# wifi_led.net
KiCad netlist of a schematic drawn in EAGLE
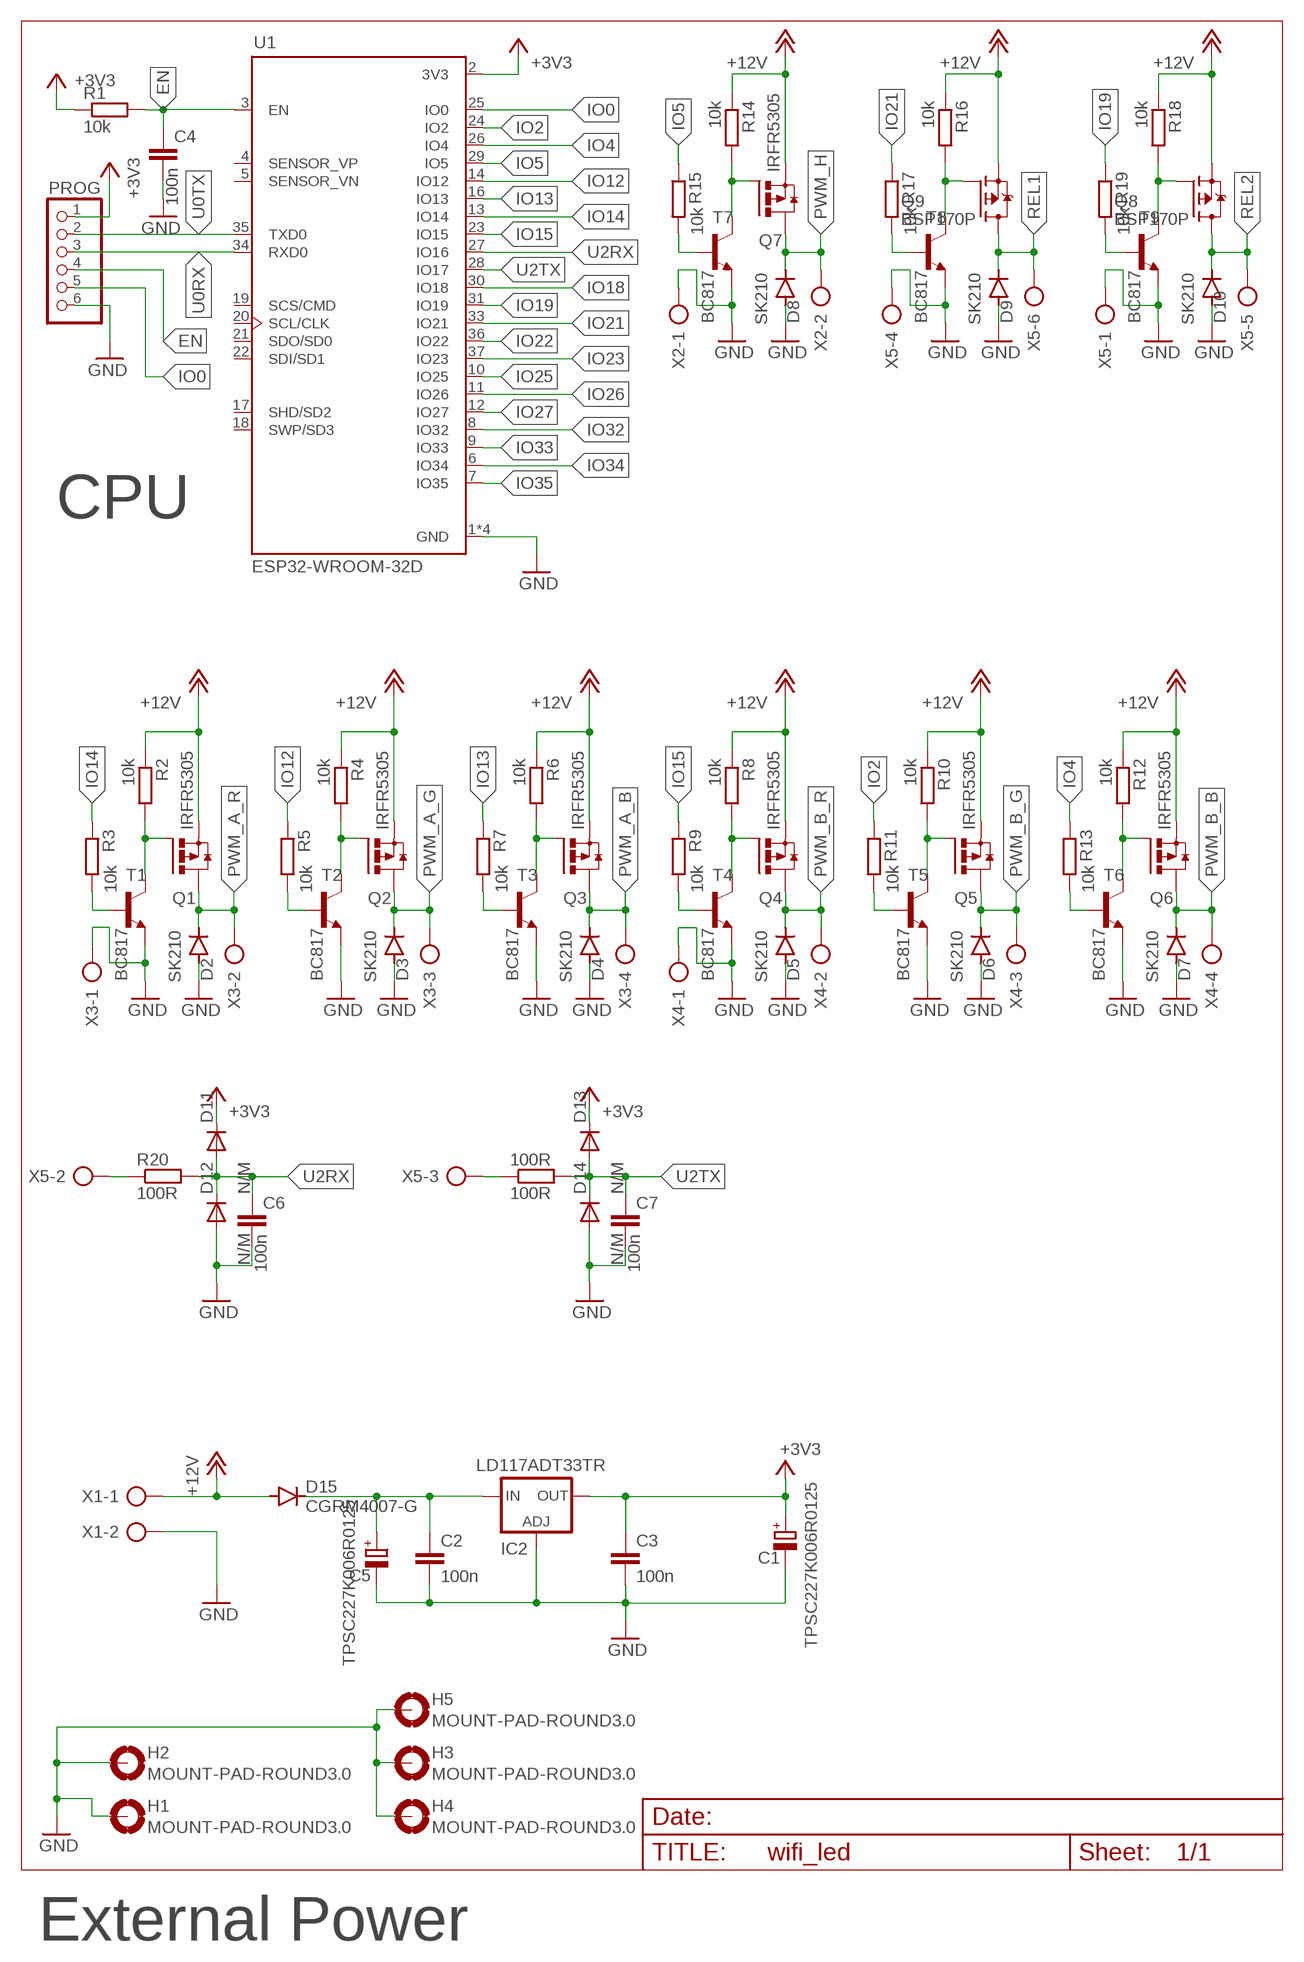
[diagram p0: schematic, sheet 1]

(export (version "E")
  (design (tool "Eeschema 10.0.6"))
  (components
    (comp (ref "100R")
      (value "100R")
      (footprint "eagle-import:R0603")
      (libsource (lib "eagle-import") (part "rcl_334_R-EU_R0603"))
    )
    (comp (ref "C1")
      (value "TPSC227K006R0125")
      (footprint "eagle-import:CT6032")
      (libsource (lib "eagle-import") (part "CPOL-EUCT6032"))
    )
    (comp (ref "C2")
      (value "100n")
      (footprint "eagle-import:C0603")
      (libsource (lib "eagle-import") (part "C-EUC0603"))
    )
    (comp (ref "C3")
      (value "100n")
      (footprint "eagle-import:C0603")
      (libsource (lib "eagle-import") (part "C-EUC0603"))
    )
    (comp (ref "C4")
      (value "100n")
      (footprint "eagle-import:C0603")
      (libsource (lib "eagle-import") (part "C-EUC0603"))
    )
    (comp (ref "C5")
      (value "TPSC227K006R0125")
      (footprint "eagle-import:CT6032")
      (libsource (lib "eagle-import") (part "CPOL-EUCT6032"))
    )
    (comp (ref "C6")
      (value "100n")
      (footprint "eagle-import:C0603")
      (libsource (lib "eagle-import") (part "C-EUC0603"))
    )
    (comp (ref "C7")
      (value "100n")
      (footprint "eagle-import:C0603")
      (libsource (lib "eagle-import") (part "C-EUC0603"))
    )
    (comp (ref "D2")
      (value "SK210")
      (footprint "eagle-import:SMB")
      (libsource (lib "eagle-import") (part "diode_210_DIODE-SMB"))
    )
    (comp (ref "D3")
      (value "SK210")
      (footprint "eagle-import:SMB")
      (libsource (lib "eagle-import") (part "diode_210_DIODE-SMB"))
    )
    (comp (ref "D4")
      (value "SK210")
      (footprint "eagle-import:SMB")
      (libsource (lib "eagle-import") (part "diode_210_DIODE-SMB"))
    )
    (comp (ref "D5")
      (value "SK210")
      (footprint "eagle-import:SMB")
      (libsource (lib "eagle-import") (part "diode_210_DIODE-SMB"))
    )
    (comp (ref "D6")
      (value "SK210")
      (footprint "eagle-import:SMB")
      (libsource (lib "eagle-import") (part "diode_210_DIODE-SMB"))
    )
    (comp (ref "D7")
      (value "SK210")
      (footprint "eagle-import:SMB")
      (libsource (lib "eagle-import") (part "diode_210_DIODE-SMB"))
    )
    (comp (ref "D8")
      (value "SK210")
      (footprint "eagle-import:SMB")
      (libsource (lib "eagle-import") (part "diode_210_DIODE-SMB"))
    )
    (comp (ref "D9")
      (value "SK210")
      (footprint "eagle-import:SMB")
      (libsource (lib "eagle-import") (part "diode_210_DIODE-SMB"))
    )
    (comp (ref "D10")
      (value "SK210")
      (footprint "eagle-import:SMB")
      (libsource (lib "eagle-import") (part "diode_210_DIODE-SMB"))
    )
    (comp (ref "D11")
      (value "N/M")
      (footprint "eagle-import:0603")
      (libsource (lib "eagle-import") (part "DIODE-SMD0603"))
    )
    (comp (ref "D12")
      (value "N/M")
      (footprint "eagle-import:0603")
      (libsource (lib "eagle-import") (part "DIODE-SMD0603"))
    )
    (comp (ref "D13")
      (value "N/M")
      (footprint "eagle-import:0603")
      (libsource (lib "eagle-import") (part "DIODE-SMD0603"))
    )
    (comp (ref "D14")
      (value "N/M")
      (footprint "eagle-import:0603")
      (libsource (lib "eagle-import") (part "DIODE-SMD0603"))
    )
    (comp (ref "D15")
      (value "CGRM4007-G")
      (footprint "eagle-import:SOD-123_MINI-SMA")
      (libsource (lib "eagle-import") (part "CGRM400-G7"))
    )
    (comp (ref "H1")
      (value "MOUNT-PAD-ROUND3.0")
      (footprint "eagle-import:3,0-PAD")
      (libsource (lib "eagle-import") (part "MOUNT-PAD-ROUND3.0"))
    )
    (comp (ref "H2")
      (value "MOUNT-PAD-ROUND3.0")
      (footprint "eagle-import:3,0-PAD")
      (libsource (lib "eagle-import") (part "MOUNT-PAD-ROUND3.0"))
    )
    (comp (ref "H3")
      (value "MOUNT-PAD-ROUND3.0")
      (footprint "eagle-import:3,0-PAD")
      (libsource (lib "eagle-import") (part "MOUNT-PAD-ROUND3.0"))
    )
    (comp (ref "H4")
      (value "MOUNT-PAD-ROUND3.0")
      (footprint "eagle-import:3,0-PAD")
      (libsource (lib "eagle-import") (part "MOUNT-PAD-ROUND3.0"))
    )
    (comp (ref "H5")
      (value "MOUNT-PAD-ROUND3.0")
      (footprint "eagle-import:3,0-PAD")
      (libsource (lib "eagle-import") (part "MOUNT-PAD-ROUND3.0"))
    )
    (comp (ref "IC2")
      (value "LD117ADT33TR")
      (footprint "eagle-import:DPACK")
      (libsource (lib "eagle-import") (part "LD117A?DT33TR"))
    )
    (comp (ref "PROG")
      (value "PINHD-1X6")
      (footprint "eagle-import:1X06")
      (libsource (lib "eagle-import") (part "PINHD-1X6"))
    )
    (comp (ref "Q1")
      (value "IRFR5305")
      (footprint "eagle-import:D-PAK")
      (libsource (lib "eagle-import") (part "IRFR5305"))
    )
    (comp (ref "Q2")
      (value "IRFR5305")
      (footprint "eagle-import:D-PAK")
      (libsource (lib "eagle-import") (part "IRFR5305"))
    )
    (comp (ref "Q3")
      (value "IRFR5305")
      (footprint "eagle-import:D-PAK")
      (libsource (lib "eagle-import") (part "IRFR5305"))
    )
    (comp (ref "Q4")
      (value "IRFR5305")
      (footprint "eagle-import:D-PAK")
      (libsource (lib "eagle-import") (part "IRFR5305"))
    )
    (comp (ref "Q5")
      (value "IRFR5305")
      (footprint "eagle-import:D-PAK")
      (libsource (lib "eagle-import") (part "IRFR5305"))
    )
    (comp (ref "Q6")
      (value "IRFR5305")
      (footprint "eagle-import:D-PAK")
      (libsource (lib "eagle-import") (part "IRFR5305"))
    )
    (comp (ref "Q7")
      (value "IRFR5305")
      (footprint "eagle-import:D-PAK")
      (libsource (lib "eagle-import") (part "IRFR5305"))
    )
    (comp (ref "Q8")
      (value "BSP170P")
      (footprint "eagle-import:SOT223")
      (libsource (lib "eagle-import") (part "BSP170P"))
    )
    (comp (ref "Q9")
      (value "BSP170P")
      (footprint "eagle-import:SOT223")
      (libsource (lib "eagle-import") (part "BSP170P"))
    )
    (comp (ref "R1")
      (value "10k")
      (footprint "eagle-import:R0603")
      (libsource (lib "eagle-import") (part "rcl_334_R-EU_R0603"))
    )
    (comp (ref "R2")
      (value "10k")
      (footprint "eagle-import:R0603")
      (libsource (lib "eagle-import") (part "R-EU_R0603"))
    )
    (comp (ref "R3")
      (value "10k")
      (footprint "eagle-import:R0603")
      (libsource (lib "eagle-import") (part "R-EU_R0603"))
    )
    (comp (ref "R4")
      (value "10k")
      (footprint "eagle-import:R0603")
      (libsource (lib "eagle-import") (part "R-EU_R0603"))
    )
    (comp (ref "R5")
      (value "10k")
      (footprint "eagle-import:R0603")
      (libsource (lib "eagle-import") (part "R-EU_R0603"))
    )
    (comp (ref "R6")
      (value "10k")
      (footprint "eagle-import:R0603")
      (libsource (lib "eagle-import") (part "R-EU_R0603"))
    )
    (comp (ref "R7")
      (value "10k")
      (footprint "eagle-import:R0603")
      (libsource (lib "eagle-import") (part "R-EU_R0603"))
    )
    (comp (ref "R8")
      (value "10k")
      (footprint "eagle-import:R0603")
      (libsource (lib "eagle-import") (part "R-EU_R0603"))
    )
    (comp (ref "R9")
      (value "10k")
      (footprint "eagle-import:R0603")
      (libsource (lib "eagle-import") (part "R-EU_R0603"))
    )
    (comp (ref "R10")
      (value "10k")
      (footprint "eagle-import:R0603")
      (libsource (lib "eagle-import") (part "R-EU_R0603"))
    )
    (comp (ref "R11")
      (value "10k")
      (footprint "eagle-import:R0603")
      (libsource (lib "eagle-import") (part "R-EU_R0603"))
    )
    (comp (ref "R12")
      (value "10k")
      (footprint "eagle-import:R0603")
      (libsource (lib "eagle-import") (part "R-EU_R0603"))
    )
    (comp (ref "R13")
      (value "10k")
      (footprint "eagle-import:R0603")
      (libsource (lib "eagle-import") (part "R-EU_R0603"))
    )
    (comp (ref "R14")
      (value "10k")
      (footprint "eagle-import:R0603")
      (libsource (lib "eagle-import") (part "R-EU_R0603"))
    )
    (comp (ref "R15")
      (value "10k")
      (footprint "eagle-import:R0603")
      (libsource (lib "eagle-import") (part "R-EU_R0603"))
    )
    (comp (ref "R16")
      (value "10k")
      (footprint "eagle-import:R0603")
      (libsource (lib "eagle-import") (part "R-EU_R0603"))
    )
    (comp (ref "R17")
      (value "10k")
      (footprint "eagle-import:R0603")
      (libsource (lib "eagle-import") (part "R-EU_R0603"))
    )
    (comp (ref "R18")
      (value "10k")
      (footprint "eagle-import:R0603")
      (libsource (lib "eagle-import") (part "R-EU_R0603"))
    )
    (comp (ref "R19")
      (value "10k")
      (footprint "eagle-import:R0603")
      (libsource (lib "eagle-import") (part "R-EU_R0603"))
    )
    (comp (ref "R20")
      (value "100R")
      (footprint "eagle-import:R0603")
      (libsource (lib "eagle-import") (part "rcl_334_R-EU_R0603"))
    )
    (comp (ref "T1")
      (value "BC817")
      (footprint "eagle-import:SOT23-BEC")
      (libsource (lib "eagle-import") (part "-NPN-SOT23-BECBC817-16"))
    )
    (comp (ref "T2")
      (value "BC817")
      (footprint "eagle-import:SOT23-BEC")
      (libsource (lib "eagle-import") (part "-NPN-SOT23-BECBC817-16"))
    )
    (comp (ref "T3")
      (value "BC817")
      (footprint "eagle-import:SOT23-BEC")
      (libsource (lib "eagle-import") (part "-NPN-SOT23-BECBC817-16"))
    )
    (comp (ref "T4")
      (value "BC817")
      (footprint "eagle-import:SOT23-BEC")
      (libsource (lib "eagle-import") (part "-NPN-SOT23-BECBC817-16"))
    )
    (comp (ref "T5")
      (value "BC817")
      (footprint "eagle-import:SOT23-BEC")
      (libsource (lib "eagle-import") (part "-NPN-SOT23-BECBC817-16"))
    )
    (comp (ref "T6")
      (value "BC817")
      (footprint "eagle-import:SOT23-BEC")
      (libsource (lib "eagle-import") (part "-NPN-SOT23-BECBC817-16"))
    )
    (comp (ref "T7")
      (value "BC817")
      (footprint "eagle-import:SOT23-BEC")
      (libsource (lib "eagle-import") (part "-NPN-SOT23-BECBC817-16"))
    )
    (comp (ref "T8")
      (value "BC817")
      (footprint "eagle-import:SOT23-BEC")
      (libsource (lib "eagle-import") (part "-NPN-SOT23-BECBC817-16"))
    )
    (comp (ref "T9")
      (value "BC817")
      (footprint "eagle-import:SOT23-BEC")
      (libsource (lib "eagle-import") (part "-NPN-SOT23-BECBC817-16"))
    )
    (comp (ref "U1")
      (value "ESP32-WROOM-32D")
      (footprint "eagle-import:MODULE_ESP32-WROOM-32D")
      (fields (field (name "MF") "Espressif Systems"))
      (libsource (lib "eagle-import") (part "ESP32-WROOM-32D"))
    )
    (comp (ref "X1")
      (value "AK500/2")
      (footprint "eagle-import:AK500_2")
      (libsource (lib "eagle-import") (part "AK500/2"))
    )
    (comp (ref "X2")
      (value "AK500/2")
      (footprint "eagle-import:AK500_2")
      (libsource (lib "eagle-import") (part "AK500/2"))
    )
    (comp (ref "X3")
      (value "AK500/4")
      (footprint "eagle-import:AK500_4")
      (libsource (lib "eagle-import") (part "AK500/4"))
    )
    (comp (ref "X4")
      (value "AK500/4")
      (footprint "eagle-import:AK500_4")
      (libsource (lib "eagle-import") (part "AK500/4"))
    )
    (comp (ref "X5")
      (value "AK500/6")
      (footprint "eagle-import:AK500_6")
      (libsource (lib "eagle-import") (part "AK500/6"))
    )
  )
  (nets
    (net (code "1") (name "+3V3") (class "Default")
      (node (ref "C1") (pin "+") (pinfunction "+_+") (pintype "passive"))
      (node (ref "C3") (pin "1") (pinfunction "1_1") (pintype "passive"))
      (node (ref "D11") (pin "2") (pinfunction "C_2") (pintype "passive"))
      (node (ref "D13") (pin "2") (pinfunction "C_2") (pintype "passive"))
      (node (ref "IC2") (pin "4") (pinfunction "OUT_4") (pintype "passive"))
      (node (ref "PROG") (pin "1") (pinfunction "1_1") (pintype "passive"))
      (node (ref "R1") (pin "1") (pinfunction "1_1") (pintype "passive"))
      (node (ref "U1") (pin "2") (pinfunction "3V3_2") (pintype "power_in"))
    )
    (net (code "2") (name "+12V") (class "Default")
      (node (ref "D15") (pin "A") (pinfunction "A_A") (pintype "passive"))
      (node (ref "Q1") (pin "3") (pinfunction "S_3") (pintype "passive"))
      (node (ref "Q2") (pin "3") (pinfunction "S_3") (pintype "passive"))
      (node (ref "Q3") (pin "3") (pinfunction "S_3") (pintype "passive"))
      (node (ref "Q4") (pin "3") (pinfunction "S_3") (pintype "passive"))
      (node (ref "Q5") (pin "3") (pinfunction "S_3") (pintype "passive"))
      (node (ref "Q6") (pin "3") (pinfunction "S_3") (pintype "passive"))
      (node (ref "Q7") (pin "3") (pinfunction "S_3") (pintype "passive"))
      (node (ref "Q8") (pin "3") (pinfunction "S_3") (pintype "passive"))
      (node (ref "Q9") (pin "3") (pinfunction "S_3") (pintype "passive"))
      (node (ref "R10") (pin "1") (pinfunction "1_1") (pintype "passive"))
      (node (ref "R12") (pin "1") (pinfunction "1_1") (pintype "passive"))
      (node (ref "R14") (pin "1") (pinfunction "1_1") (pintype "passive"))
      (node (ref "R16") (pin "1") (pinfunction "1_1") (pintype "passive"))
      (node (ref "R18") (pin "1") (pinfunction "1_1") (pintype "passive"))
      (node (ref "R2") (pin "1") (pinfunction "1_1") (pintype "passive"))
      (node (ref "R4") (pin "1") (pinfunction "1_1") (pintype "passive"))
      (node (ref "R6") (pin "1") (pinfunction "1_1") (pintype "passive"))
      (node (ref "R8") (pin "1") (pinfunction "1_1") (pintype "passive"))
      (node (ref "X1") (pin "1") (pinfunction "KL_1") (pintype "passive"))
    )
    (net (code "3") (name "EN") (class "Default")
      (node (ref "C4") (pin "1") (pinfunction "1_1") (pintype "passive"))
      (node (ref "PROG") (pin "4") (pinfunction "4_4") (pintype "passive"))
      (node (ref "R1") (pin "2") (pinfunction "2_2") (pintype "passive"))
      (node (ref "U1") (pin "3") (pinfunction "EN_3") (pintype "input"))
    )
    (net (code "4") (name "GND") (class "Default")
      (node (ref "C1") (pin "-") (pinfunction "-_-") (pintype "passive"))
      (node (ref "C2") (pin "2") (pinfunction "2_2") (pintype "passive"))
      (node (ref "C3") (pin "2") (pinfunction "2_2") (pintype "passive"))
      (node (ref "C4") (pin "2") (pinfunction "2_2") (pintype "passive"))
      (node (ref "C5") (pin "-") (pinfunction "-_-") (pintype "passive"))
      (node (ref "C6") (pin "2") (pinfunction "2_2") (pintype "passive"))
      (node (ref "C7") (pin "2") (pinfunction "2_2") (pintype "passive"))
      (node (ref "D10") (pin "A") (pinfunction "A_A") (pintype "passive"))
      (node (ref "D12") (pin "1") (pinfunction "A_1") (pintype "passive"))
      (node (ref "D14") (pin "1") (pinfunction "A_1") (pintype "passive"))
      (node (ref "D2") (pin "A") (pinfunction "A_A") (pintype "passive"))
      (node (ref "D3") (pin "A") (pinfunction "A_A") (pintype "passive"))
      (node (ref "D4") (pin "A") (pinfunction "A_A") (pintype "passive"))
      (node (ref "D5") (pin "A") (pinfunction "A_A") (pintype "passive"))
      (node (ref "D6") (pin "A") (pinfunction "A_A") (pintype "passive"))
      (node (ref "D7") (pin "A") (pinfunction "A_A") (pintype "passive"))
      (node (ref "D8") (pin "A") (pinfunction "A_A") (pintype "passive"))
      (node (ref "D9") (pin "A") (pinfunction "A_A") (pintype "passive"))
      (node (ref "H1") (pin "B3,0") (pinfunction "MOUNT_B3,0") (pintype "passive"))
      (node (ref "H2") (pin "B3,0") (pinfunction "MOUNT_B3,0") (pintype "passive"))
      (node (ref "H3") (pin "B3,0") (pinfunction "MOUNT_B3,0") (pintype "passive"))
      (node (ref "H4") (pin "B3,0") (pinfunction "MOUNT_B3,0") (pintype "passive"))
      (node (ref "H5") (pin "B3,0") (pinfunction "MOUNT_B3,0") (pintype "passive"))
      (node (ref "IC2") (pin "1") (pinfunction "ADJ_1") (pintype "input"))
      (node (ref "PROG") (pin "6") (pinfunction "6_6") (pintype "passive"))
      (node (ref "T1") (pin "E") (pinfunction "E_E") (pintype "passive"))
      (node (ref "T2") (pin "E") (pinfunction "E_E") (pintype "passive"))
      (node (ref "T3") (pin "E") (pinfunction "E_E") (pintype "passive"))
      (node (ref "T4") (pin "E") (pinfunction "E_E") (pintype "passive"))
      (node (ref "T5") (pin "E") (pinfunction "E_E") (pintype "passive"))
      (node (ref "T6") (pin "E") (pinfunction "E_E") (pintype "passive"))
      (node (ref "T7") (pin "E") (pinfunction "E_E") (pintype "passive"))
      (node (ref "T8") (pin "E") (pinfunction "E_E") (pintype "passive"))
      (node (ref "T9") (pin "E") (pinfunction "E_E") (pintype "passive"))
      (node (ref "U1") (pin "1") (pinfunction "GND_1") (pintype "power_in"))
      (node (ref "U1") (pin "15") (pinfunction "GND_15") (pintype "power_in"))
      (node (ref "U1") (pin "38") (pinfunction "GND_38") (pintype "power_in"))
      (node (ref "U1") (pin "39") (pinfunction "GND_39") (pintype "power_in"))
      (node (ref "X1") (pin "2") (pinfunction "KL_2") (pintype "passive"))
      (node (ref "X2") (pin "1") (pinfunction "KL_1") (pintype "passive"))
      (node (ref "X3") (pin "1") (pinfunction "KL_1") (pintype "passive"))
      (node (ref "X4") (pin "1") (pinfunction "KL_1") (pintype "passive"))
      (node (ref "X5") (pin "1") (pinfunction "KL_1") (pintype "passive"))
      (node (ref "X5") (pin "4") (pinfunction "KL_4") (pintype "passive"))
    )
    (net (code "5") (name "IO0") (class "Default")
      (node (ref "PROG") (pin "5") (pinfunction "5_5") (pintype "passive"))
      (node (ref "U1") (pin "25") (pinfunction "IO0_25") (pintype "bidirectional"))
    )
    (net (code "6") (name "IO2") (class "Default")
      (node (ref "R11") (pin "1") (pinfunction "1_1") (pintype "passive"))
      (node (ref "U1") (pin "24") (pinfunction "IO2_24") (pintype "bidirectional"))
    )
    (net (code "7") (name "IO4") (class "Default")
      (node (ref "R13") (pin "1") (pinfunction "1_1") (pintype "passive"))
      (node (ref "U1") (pin "26") (pinfunction "IO4_26") (pintype "bidirectional"))
    )
    (net (code "8") (name "IO5") (class "Default")
      (node (ref "R15") (pin "1") (pinfunction "1_1") (pintype "passive"))
      (node (ref "U1") (pin "29") (pinfunction "IO5_29") (pintype "bidirectional"))
    )
    (net (code "9") (name "IO12") (class "Default")
      (node (ref "R5") (pin "1") (pinfunction "1_1") (pintype "passive"))
      (node (ref "U1") (pin "14") (pinfunction "IO12_14") (pintype "bidirectional"))
    )
    (net (code "10") (name "IO13") (class "Default")
      (node (ref "R7") (pin "1") (pinfunction "1_1") (pintype "passive"))
      (node (ref "U1") (pin "16") (pinfunction "IO13_16") (pintype "bidirectional"))
    )
    (net (code "11") (name "IO14") (class "Default")
      (node (ref "R3") (pin "1") (pinfunction "1_1") (pintype "passive"))
      (node (ref "U1") (pin "13") (pinfunction "IO14_13") (pintype "bidirectional"))
    )
    (net (code "12") (name "IO15") (class "Default")
      (node (ref "R9") (pin "1") (pinfunction "1_1") (pintype "passive"))
      (node (ref "U1") (pin "23") (pinfunction "IO15_23") (pintype "bidirectional"))
    )
    (net (code "13") (name "IO18") (class "Default")
      (node (ref "U1") (pin "30") (pinfunction "IO18_30") (pintype "bidirectional"))
    )
    (net (code "14") (name "IO19") (class "Default")
      (node (ref "R19") (pin "1") (pinfunction "1_1") (pintype "passive"))
      (node (ref "U1") (pin "31") (pinfunction "IO19_31") (pintype "bidirectional"))
    )
    (net (code "15") (name "IO21") (class "Default")
      (node (ref "R17") (pin "1") (pinfunction "1_1") (pintype "passive"))
      (node (ref "U1") (pin "33") (pinfunction "IO21_33") (pintype "bidirectional"))
    )
    (net (code "16") (name "IO22") (class "Default")
      (node (ref "U1") (pin "36") (pinfunction "IO22_36") (pintype "bidirectional"))
    )
    (net (code "17") (name "IO23") (class "Default")
      (node (ref "U1") (pin "37") (pinfunction "IO23_37") (pintype "bidirectional"))
    )
    (net (code "18") (name "IO25") (class "Default")
      (node (ref "U1") (pin "10") (pinfunction "IO25_10") (pintype "bidirectional"))
    )
    (net (code "19") (name "IO26") (class "Default")
      (node (ref "U1") (pin "11") (pinfunction "IO26_11") (pintype "bidirectional"))
    )
    (net (code "20") (name "IO27") (class "Default")
      (node (ref "U1") (pin "12") (pinfunction "IO27_12") (pintype "bidirectional"))
    )
    (net (code "21") (name "IO32") (class "Default")
      (node (ref "U1") (pin "8") (pinfunction "IO32_8") (pintype "bidirectional"))
    )
    (net (code "22") (name "IO33") (class "Default")
      (node (ref "U1") (pin "9") (pinfunction "IO33_9") (pintype "bidirectional"))
    )
    (net (code "23") (name "IO34") (class "Default")
      (node (ref "U1") (pin "6") (pinfunction "IO34_6") (pintype "bidirectional"))
    )
    (net (code "24") (name "IO35") (class "Default")
      (node (ref "U1") (pin "7") (pinfunction "IO35_7") (pintype "bidirectional"))
    )
    (net (code "25") (name "Net-(IC2-IN)") (class "Default")
      (node (ref "C2") (pin "1") (pinfunction "1_1") (pintype "passive"))
      (node (ref "C5") (pin "+") (pinfunction "+_+") (pintype "passive"))
      (node (ref "D15") (pin "C") (pinfunction "C_C") (pintype "passive"))
      (node (ref "IC2") (pin "3") (pinfunction "IN_3") (pintype "input"))
    )
    (net (code "26") (name "Net-(Q1-G)") (class "Default")
      (node (ref "Q1") (pin "1") (pinfunction "G_1") (pintype "passive"))
      (node (ref "R2") (pin "2") (pinfunction "2_2") (pintype "passive"))
      (node (ref "T1") (pin "C") (pinfunction "C_C") (pintype "passive"))
    )
    (net (code "27") (name "Net-(Q2-G)") (class "Default")
      (node (ref "Q2") (pin "1") (pinfunction "G_1") (pintype "passive"))
      (node (ref "R4") (pin "2") (pinfunction "2_2") (pintype "passive"))
      (node (ref "T2") (pin "C") (pinfunction "C_C") (pintype "passive"))
    )
    (net (code "28") (name "Net-(Q3-G)") (class "Default")
      (node (ref "Q3") (pin "1") (pinfunction "G_1") (pintype "passive"))
      (node (ref "R6") (pin "2") (pinfunction "2_2") (pintype "passive"))
      (node (ref "T3") (pin "C") (pinfunction "C_C") (pintype "passive"))
    )
    (net (code "29") (name "Net-(Q4-G)") (class "Default")
      (node (ref "Q4") (pin "1") (pinfunction "G_1") (pintype "passive"))
      (node (ref "R8") (pin "2") (pinfunction "2_2") (pintype "passive"))
      (node (ref "T4") (pin "C") (pinfunction "C_C") (pintype "passive"))
    )
    (net (code "30") (name "Net-(Q5-G)") (class "Default")
      (node (ref "Q5") (pin "1") (pinfunction "G_1") (pintype "passive"))
      (node (ref "R10") (pin "2") (pinfunction "2_2") (pintype "passive"))
      (node (ref "T5") (pin "C") (pinfunction "C_C") (pintype "passive"))
    )
    (net (code "31") (name "Net-(Q6-G)") (class "Default")
      (node (ref "Q6") (pin "1") (pinfunction "G_1") (pintype "passive"))
      (node (ref "R12") (pin "2") (pinfunction "2_2") (pintype "passive"))
      (node (ref "T6") (pin "C") (pinfunction "C_C") (pintype "passive"))
    )
    (net (code "32") (name "Net-(Q7-G)") (class "Default")
      (node (ref "Q7") (pin "1") (pinfunction "G_1") (pintype "passive"))
      (node (ref "R14") (pin "2") (pinfunction "2_2") (pintype "passive"))
      (node (ref "T7") (pin "C") (pinfunction "C_C") (pintype "passive"))
    )
    (net (code "33") (name "Net-(Q8-G)") (class "Default")
      (node (ref "Q8") (pin "1") (pinfunction "G_1") (pintype "passive"))
      (node (ref "R18") (pin "2") (pinfunction "2_2") (pintype "passive"))
      (node (ref "T9") (pin "C") (pinfunction "C_C") (pintype "passive"))
    )
    (net (code "34") (name "Net-(Q9-G)") (class "Default")
      (node (ref "Q9") (pin "1") (pinfunction "G_1") (pintype "passive"))
      (node (ref "R16") (pin "2") (pinfunction "2_2") (pintype "passive"))
      (node (ref "T8") (pin "C") (pinfunction "C_C") (pintype "passive"))
    )
    (net (code "35") (name "Net-(R3-Pad2)") (class "Default")
      (node (ref "R3") (pin "2") (pinfunction "2_2") (pintype "passive"))
      (node (ref "T1") (pin "B") (pinfunction "B_B") (pintype "passive"))
    )
    (net (code "36") (name "Net-(R5-Pad2)") (class "Default")
      (node (ref "R5") (pin "2") (pinfunction "2_2") (pintype "passive"))
      (node (ref "T2") (pin "B") (pinfunction "B_B") (pintype "passive"))
    )
    (net (code "37") (name "Net-(R7-Pad2)") (class "Default")
      (node (ref "R7") (pin "2") (pinfunction "2_2") (pintype "passive"))
      (node (ref "T3") (pin "B") (pinfunction "B_B") (pintype "passive"))
    )
    (net (code "38") (name "Net-(R9-Pad2)") (class "Default")
      (node (ref "R9") (pin "2") (pinfunction "2_2") (pintype "passive"))
      (node (ref "T4") (pin "B") (pinfunction "B_B") (pintype "passive"))
    )
    (net (code "39") (name "Net-(R11-Pad2)") (class "Default")
      (node (ref "R11") (pin "2") (pinfunction "2_2") (pintype "passive"))
      (node (ref "T5") (pin "B") (pinfunction "B_B") (pintype "passive"))
    )
    (net (code "40") (name "Net-(R13-Pad2)") (class "Default")
      (node (ref "R13") (pin "2") (pinfunction "2_2") (pintype "passive"))
      (node (ref "T6") (pin "B") (pinfunction "B_B") (pintype "passive"))
    )
    (net (code "41") (name "Net-(R15-Pad2)") (class "Default")
      (node (ref "R15") (pin "2") (pinfunction "2_2") (pintype "passive"))
      (node (ref "T7") (pin "B") (pinfunction "B_B") (pintype "passive"))
    )
    (net (code "42") (name "Net-(R17-Pad2)") (class "Default")
      (node (ref "R17") (pin "2") (pinfunction "2_2") (pintype "passive"))
      (node (ref "T8") (pin "B") (pinfunction "B_B") (pintype "passive"))
    )
    (net (code "43") (name "Net-(R19-Pad2)") (class "Default")
      (node (ref "R19") (pin "2") (pinfunction "2_2") (pintype "passive"))
      (node (ref "T9") (pin "B") (pinfunction "B_B") (pintype "passive"))
    )
    (net (code "44") (name "Net-(X5B-KL)") (class "Default")
      (node (ref "R20") (pin "1") (pinfunction "1_1") (pintype "passive"))
      (node (ref "X5") (pin "2") (pinfunction "KL_2") (pintype "passive"))
    )
    (net (code "45") (name "Net-(X5C-KL)") (class "Default")
      (node (ref "100R") (pin "1") (pinfunction "1_1") (pintype "passive"))
      (node (ref "X5") (pin "3") (pinfunction "KL_3") (pintype "passive"))
    )
    (net (code "46") (name "PWM_A_B") (class "Default")
      (node (ref "D4") (pin "C") (pinfunction "C_C") (pintype "passive"))
      (node (ref "Q3") (pin "4") (pinfunction "D_4") (pintype "passive"))
      (node (ref "X3") (pin "4") (pinfunction "KL_4") (pintype "passive"))
    )
    (net (code "47") (name "PWM_A_G") (class "Default")
      (node (ref "D3") (pin "C") (pinfunction "C_C") (pintype "passive"))
      (node (ref "Q2") (pin "4") (pinfunction "D_4") (pintype "passive"))
      (node (ref "X3") (pin "3") (pinfunction "KL_3") (pintype "passive"))
    )
    (net (code "48") (name "PWM_A_R") (class "Default")
      (node (ref "D2") (pin "C") (pinfunction "C_C") (pintype "passive"))
      (node (ref "Q1") (pin "4") (pinfunction "D_4") (pintype "passive"))
      (node (ref "X3") (pin "2") (pinfunction "KL_2") (pintype "passive"))
    )
    (net (code "49") (name "PWM_B_B") (class "Default")
      (node (ref "D7") (pin "C") (pinfunction "C_C") (pintype "passive"))
      (node (ref "Q6") (pin "4") (pinfunction "D_4") (pintype "passive"))
      (node (ref "X4") (pin "4") (pinfunction "KL_4") (pintype "passive"))
    )
    (net (code "50") (name "PWM_B_G") (class "Default")
      (node (ref "D6") (pin "C") (pinfunction "C_C") (pintype "passive"))
      (node (ref "Q5") (pin "4") (pinfunction "D_4") (pintype "passive"))
      (node (ref "X4") (pin "3") (pinfunction "KL_3") (pintype "passive"))
    )
    (net (code "51") (name "PWM_B_R") (class "Default")
      (node (ref "D5") (pin "C") (pinfunction "C_C") (pintype "passive"))
      (node (ref "Q4") (pin "4") (pinfunction "D_4") (pintype "passive"))
      (node (ref "X4") (pin "2") (pinfunction "KL_2") (pintype "passive"))
    )
    (net (code "52") (name "PWM_H") (class "Default")
      (node (ref "D8") (pin "C") (pinfunction "C_C") (pintype "passive"))
      (node (ref "Q7") (pin "4") (pinfunction "D_4") (pintype "passive"))
      (node (ref "X2") (pin "2") (pinfunction "KL_2") (pintype "passive"))
    )
    (net (code "53") (name "REL1") (class "Default")
      (node (ref "D9") (pin "C") (pinfunction "C_C") (pintype "passive"))
      (node (ref "Q9") (pin "2") (pinfunction "D_2") (pintype "passive"))
      (node (ref "Q9") (pin "4") (pinfunction "D_4") (pintype "passive"))
      (node (ref "X5") (pin "6") (pinfunction "KL_6") (pintype "passive"))
    )
    (net (code "54") (name "REL2") (class "Default")
      (node (ref "D10") (pin "C") (pinfunction "C_C") (pintype "passive"))
      (node (ref "Q8") (pin "2") (pinfunction "D_2") (pintype "passive"))
      (node (ref "Q8") (pin "4") (pinfunction "D_4") (pintype "passive"))
      (node (ref "X5") (pin "5") (pinfunction "KL_5") (pintype "passive"))
    )
    (net (code "55") (name "U0RX") (class "Default")
      (node (ref "PROG") (pin "3") (pinfunction "3_3") (pintype "passive"))
      (node (ref "U1") (pin "34") (pinfunction "RXD0_34") (pintype "bidirectional"))
    )
    (net (code "56") (name "U0TX") (class "Default")
      (node (ref "PROG") (pin "2") (pinfunction "2_2") (pintype "passive"))
      (node (ref "U1") (pin "35") (pinfunction "TXD0_35") (pintype "bidirectional"))
    )
    (net (code "57") (name "U2RX") (class "Default")
      (node (ref "C6") (pin "1") (pinfunction "1_1") (pintype "passive"))
      (node (ref "D11") (pin "1") (pinfunction "A_1") (pintype "passive"))
      (node (ref "D12") (pin "2") (pinfunction "C_2") (pintype "passive"))
      (node (ref "R20") (pin "2") (pinfunction "2_2") (pintype "passive"))
      (node (ref "U1") (pin "27") (pinfunction "IO16_27") (pintype "bidirectional"))
    )
    (net (code "58") (name "U2TX") (class "Default")
      (node (ref "100R") (pin "2") (pinfunction "2_2") (pintype "passive"))
      (node (ref "C7") (pin "1") (pinfunction "1_1") (pintype "passive"))
      (node (ref "D13") (pin "1") (pinfunction "A_1") (pintype "passive"))
      (node (ref "D14") (pin "2") (pinfunction "C_2") (pintype "passive"))
      (node (ref "U1") (pin "28") (pinfunction "IO17_28") (pintype "bidirectional"))
    )
    (net (code "59") (name "unconnected-(U1-SCL{slash}CLK-Pad20)") (class "Default")
      (node (ref "U1") (pin "20") (pinfunction "SCL/CLK_20") (pintype "bidirectional"))
    )
    (net (code "60") (name "unconnected-(U1-SCS{slash}CMD-Pad19)") (class "Default")
      (node (ref "U1") (pin "19") (pinfunction "SCS/CMD_19") (pintype "bidirectional"))
    )
    (net (code "61") (name "unconnected-(U1-SDI{slash}SD1-Pad22)") (class "Default")
      (node (ref "U1") (pin "22") (pinfunction "SDI/SD1_22") (pintype "bidirectional"))
    )
    (net (code "62") (name "unconnected-(U1-SDO{slash}SD0-Pad21)") (class "Default")
      (node (ref "U1") (pin "21") (pinfunction "SDO/SD0_21") (pintype "bidirectional"))
    )
    (net (code "63") (name "unconnected-(U1-SENSOR_VN-Pad5)") (class "Default")
      (node (ref "U1") (pin "5") (pinfunction "SENSOR_VN_5") (pintype "input"))
    )
    (net (code "64") (name "unconnected-(U1-SENSOR_VP-Pad4)") (class "Default")
      (node (ref "U1") (pin "4") (pinfunction "SENSOR_VP_4") (pintype "input"))
    )
    (net (code "65") (name "unconnected-(U1-SHD{slash}SD2-Pad17)") (class "Default")
      (node (ref "U1") (pin "17") (pinfunction "SHD/SD2_17") (pintype "bidirectional"))
    )
    (net (code "66") (name "unconnected-(U1-SWP{slash}SD3-Pad18)") (class "Default")
      (node (ref "U1") (pin "18") (pinfunction "SWP/SD3_18") (pintype "bidirectional"))
    )
  )
)
